# STM32.net
KiCad netlist of a schematic drawn in EasyEDA Pro
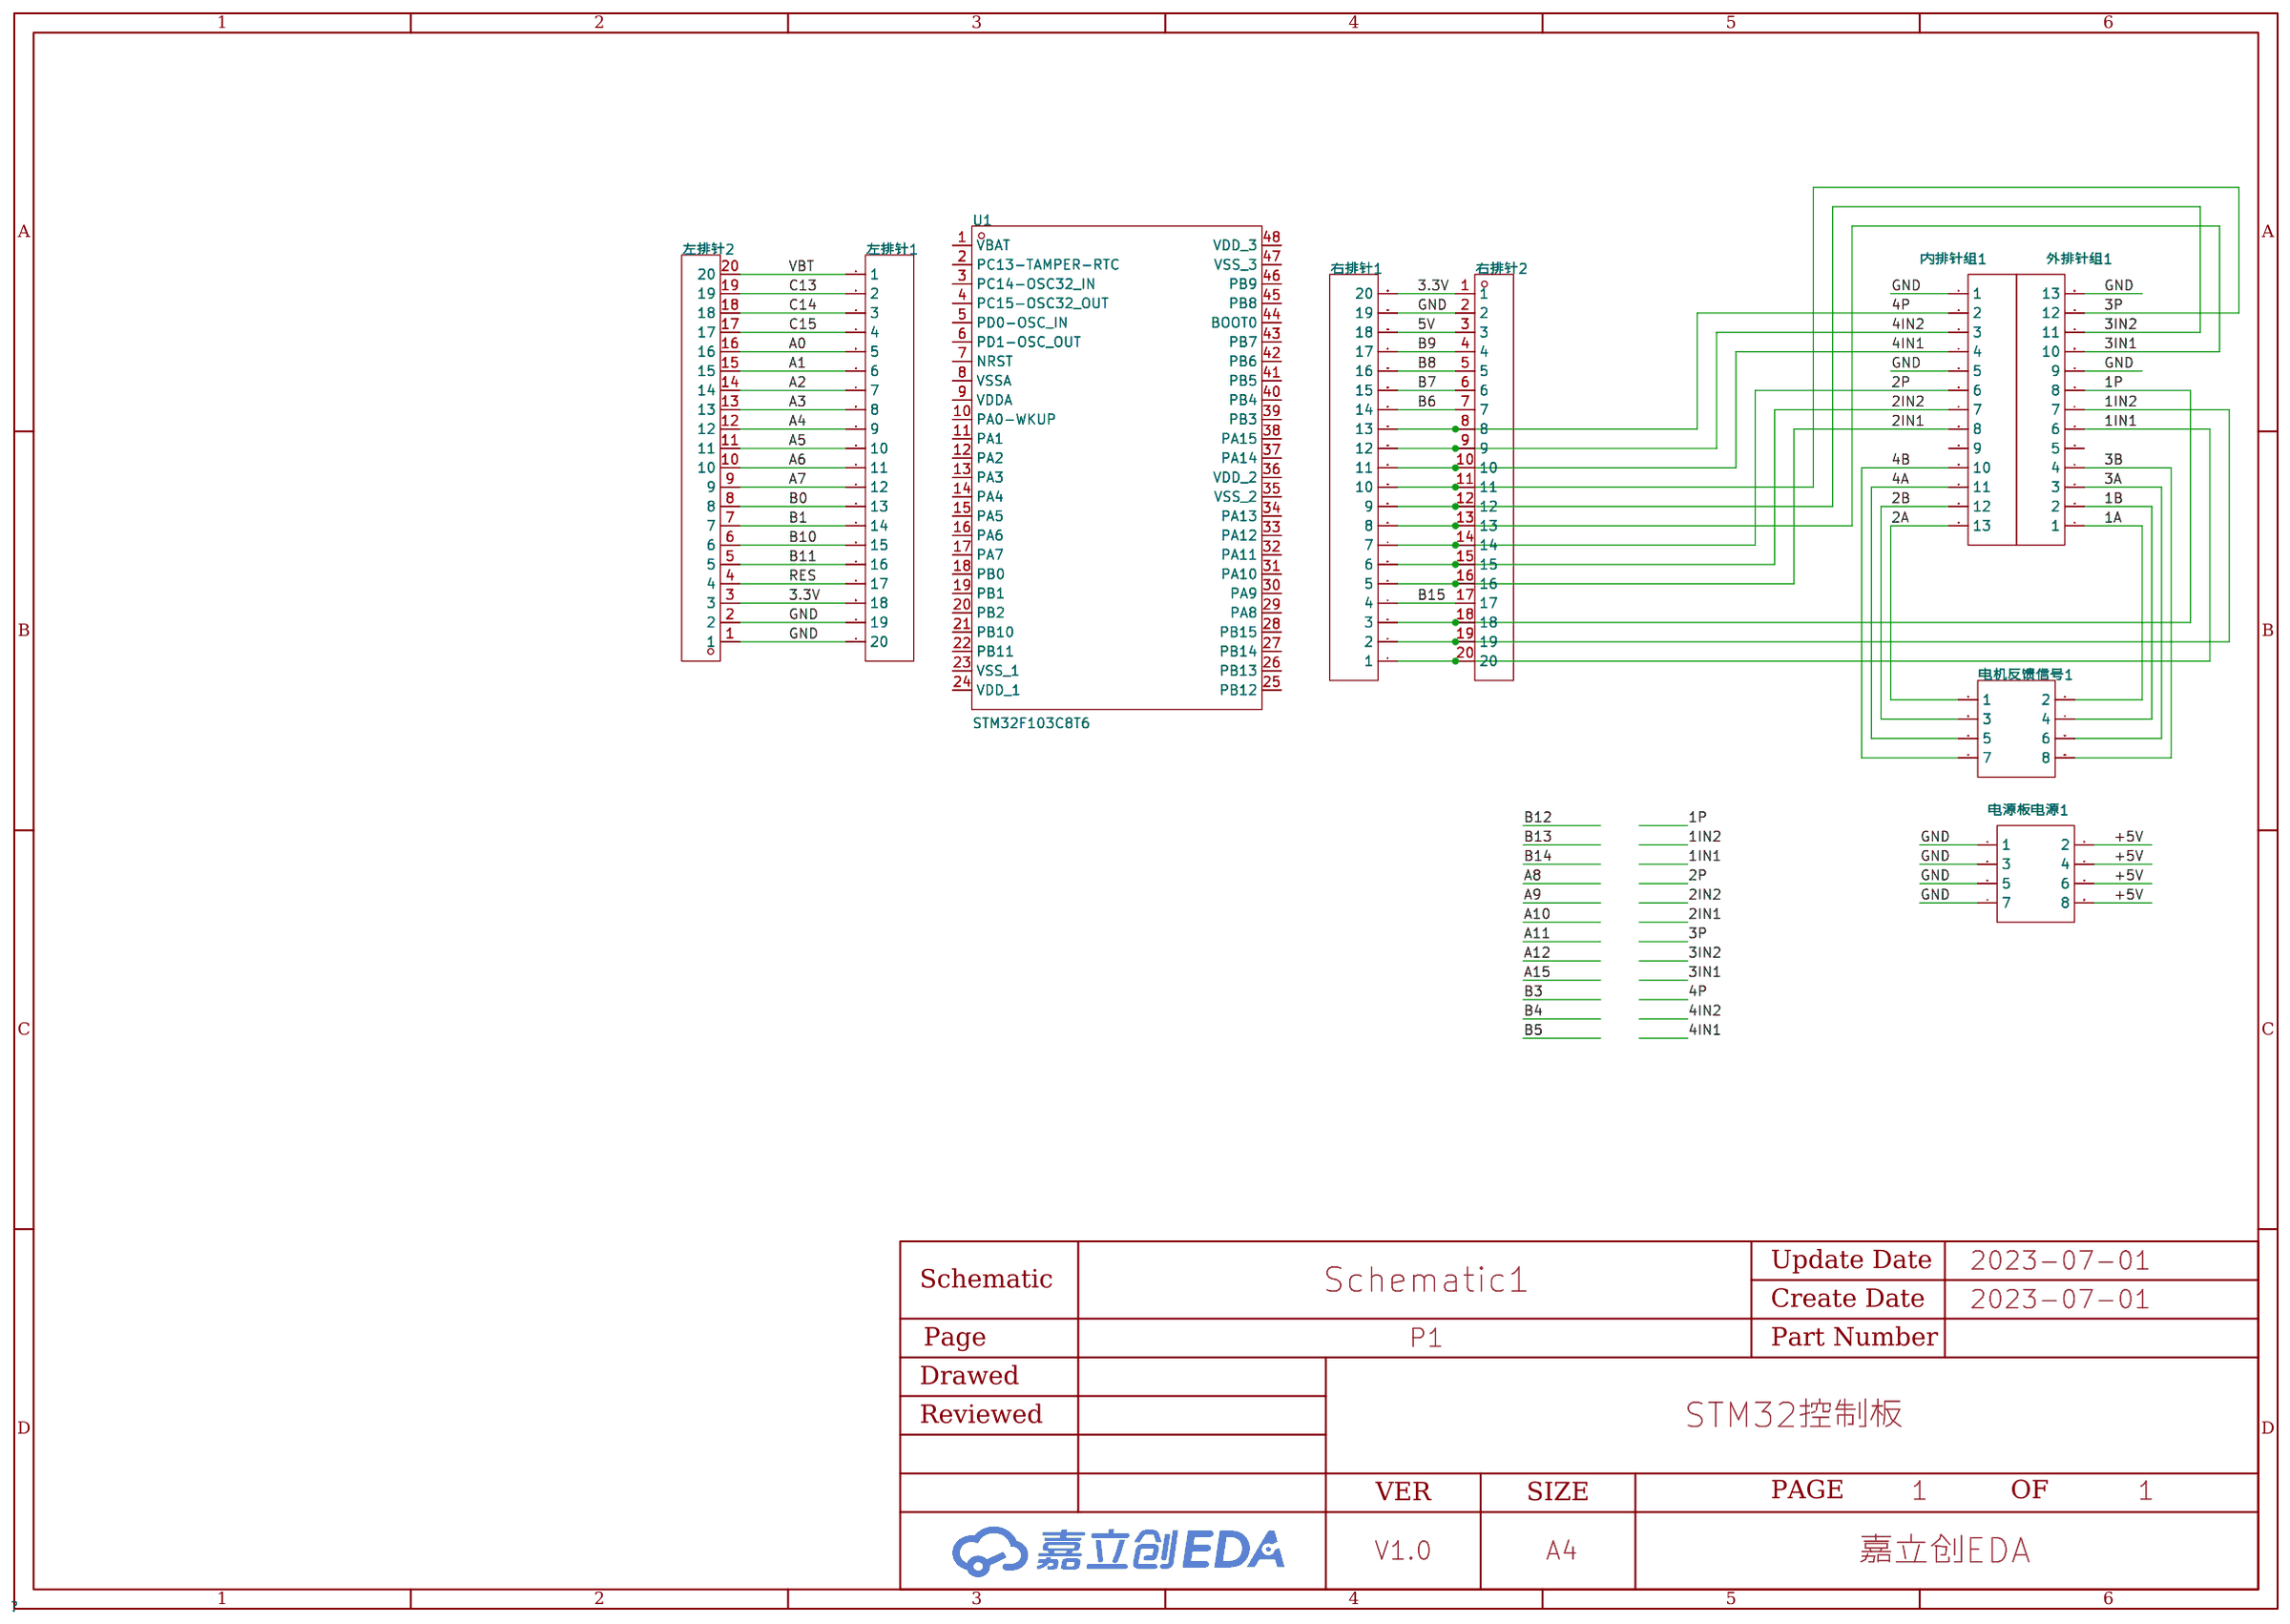
[diagram p0: schematic sheet]

(export (version "E")
  (design (tool "Eeschema 10.0.6"))
  (components
    (comp (ref "U1")
      (value "STM32F103C8T6")
      (footprint "easyedapro:LQFP-48_L7.0-W7.0-P0.50-LS9.0-BL")
      (description "CPU内核:ARM Cortex-M3;CPU最大主频:72MHz;程序存储容量:64KB;程序存储器类型:FLASH;RAM总容量:20KB;GPIO端口数量:37;")
      (fields (field (name "Manufacturer") "ST(意法半导体)"))
      (libsource (lib "easyedapro") (part "STM32F103C8T6"))
    )
    (comp (ref "内排针组1")
      (value "~")
      (footprint "easyedapro:HDR-TH_13P-P2.54-V-F")
      (libsource (lib "easyedapro") (part "HDR-F_2.54_1x13P"))
    )
    (comp (ref "右排针1")
      (value "~")
      (footprint "easyedapro:HDR-TH_20P-P2.54-V-F")
      (libsource (lib "easyedapro") (part "HDR-F_2.54_1x20P"))
    )
    (comp (ref "右排针2")
      (value "~")
      (footprint "easyedapro:HDR-TH_20P-P2.54-V-M-1")
      (libsource (lib "easyedapro") (part "HDR_2.54-1x20P"))
    )
    (comp (ref "外排针组1")
      (value "~")
      (footprint "easyedapro:HDR-TH_13P-P2.54-V-F")
      (libsource (lib "easyedapro") (part "HDR-F_2.54_1x13P"))
    )
    (comp (ref "左排针1")
      (value "~")
      (footprint "easyedapro:HDR-TH_20P-P2.54-V-F")
      (libsource (lib "easyedapro") (part "HDR-F_2.54_1x20P"))
    )
    (comp (ref "左排针2")
      (value "~")
      (footprint "easyedapro:HDR-TH_20P-P2.54-V-M-1")
      (libsource (lib "easyedapro") (part "HDR_2.54-1x20P"))
    )
    (comp (ref "电机反馈信号1")
      (value "~")
      (footprint "easyedapro:HDR-TH_8P-P2.54-V-F-R2-C4-S2.54-1")
      (libsource (lib "easyedapro") (part "HDR-F-2.54_2x4"))
    )
    (comp (ref "电源板电源1")
      (value "~")
      (footprint "easyedapro:HDR-TH_8P-P2.54-V-F-R2-C4-S2.54-1")
      (libsource (lib "easyedapro") (part "HDR-F-2.54_2x4"))
    )
  )
  (nets
    (net (code "1") (name "/+5V") (class "Default")
      (node (ref "电源板电源1") (pin "2") (pinfunction "2_2") (pintype "input"))
      (node (ref "电源板电源1") (pin "4") (pinfunction "4_4") (pintype "input"))
      (node (ref "电源板电源1") (pin "6") (pinfunction "6_6") (pintype "input"))
      (node (ref "电源板电源1") (pin "8") (pinfunction "8_8") (pintype "input"))
    )
    (net (code "2") (name "/1A") (class "Default")
      (node (ref "外排针组1") (pin "1") (pinfunction "1_1") (pintype "input"))
      (node (ref "电机反馈信号1") (pin "2") (pinfunction "2_2") (pintype "input"))
    )
    (net (code "3") (name "/1B") (class "Default")
      (node (ref "外排针组1") (pin "2") (pinfunction "2_2") (pintype "input"))
      (node (ref "电机反馈信号1") (pin "4") (pinfunction "4_4") (pintype "input"))
    )
    (net (code "4") (name "/1IN1") (class "Default")
      (node (ref "右排针1") (pin "1") (pinfunction "1_1") (pintype "input"))
      (node (ref "右排针2") (pin "20") (pinfunction "20_20") (pintype "input"))
      (node (ref "外排针组1") (pin "6") (pinfunction "6_6") (pintype "input"))
    )
    (net (code "5") (name "/1IN2") (class "Default")
      (node (ref "右排针1") (pin "2") (pinfunction "2_2") (pintype "input"))
      (node (ref "右排针2") (pin "19") (pinfunction "19_19") (pintype "input"))
      (node (ref "外排针组1") (pin "7") (pinfunction "7_7") (pintype "input"))
    )
    (net (code "6") (name "/1P") (class "Default")
      (node (ref "右排针1") (pin "3") (pinfunction "3_3") (pintype "input"))
      (node (ref "右排针2") (pin "18") (pinfunction "18_18") (pintype "input"))
      (node (ref "外排针组1") (pin "8") (pinfunction "8_8") (pintype "input"))
    )
    (net (code "7") (name "/2A") (class "Default")
      (node (ref "内排针组1") (pin "13") (pinfunction "13_13") (pintype "input"))
      (node (ref "电机反馈信号1") (pin "1") (pinfunction "1_1") (pintype "input"))
    )
    (net (code "8") (name "/2B") (class "Default")
      (node (ref "内排针组1") (pin "12") (pinfunction "12_12") (pintype "input"))
      (node (ref "电机反馈信号1") (pin "3") (pinfunction "3_3") (pintype "input"))
    )
    (net (code "9") (name "/2IN1") (class "Default")
      (node (ref "内排针组1") (pin "8") (pinfunction "8_8") (pintype "input"))
      (node (ref "右排针1") (pin "5") (pinfunction "5_5") (pintype "input"))
      (node (ref "右排针2") (pin "16") (pinfunction "16_16") (pintype "input"))
    )
    (net (code "10") (name "/2IN2") (class "Default")
      (node (ref "内排针组1") (pin "7") (pinfunction "7_7") (pintype "input"))
      (node (ref "右排针1") (pin "6") (pinfunction "6_6") (pintype "input"))
      (node (ref "右排针2") (pin "15") (pinfunction "15_15") (pintype "input"))
    )
    (net (code "11") (name "/2P") (class "Default")
      (node (ref "内排针组1") (pin "6") (pinfunction "6_6") (pintype "input"))
      (node (ref "右排针1") (pin "7") (pinfunction "7_7") (pintype "input"))
      (node (ref "右排针2") (pin "14") (pinfunction "14_14") (pintype "input"))
    )
    (net (code "12") (name "/3.3V") (class "Default")
      (node (ref "右排针1") (pin "20") (pinfunction "20_20") (pintype "input"))
      (node (ref "右排针2") (pin "1") (pinfunction "1_1") (pintype "input"))
      (node (ref "左排针1") (pin "18") (pinfunction "18_18") (pintype "input"))
      (node (ref "左排针2") (pin "3") (pinfunction "3_3") (pintype "input"))
    )
    (net (code "13") (name "/3A") (class "Default")
      (node (ref "外排针组1") (pin "3") (pinfunction "3_3") (pintype "input"))
      (node (ref "电机反馈信号1") (pin "6") (pinfunction "6_6") (pintype "input"))
    )
    (net (code "14") (name "/3B") (class "Default")
      (node (ref "外排针组1") (pin "4") (pinfunction "4_4") (pintype "input"))
      (node (ref "电机反馈信号1") (pin "8") (pinfunction "8_8") (pintype "input"))
    )
    (net (code "15") (name "/3IN1") (class "Default")
      (node (ref "右排针1") (pin "8") (pinfunction "8_8") (pintype "input"))
      (node (ref "右排针2") (pin "13") (pinfunction "13_13") (pintype "input"))
      (node (ref "外排针组1") (pin "10") (pinfunction "10_10") (pintype "input"))
    )
    (net (code "16") (name "/3IN2") (class "Default")
      (node (ref "右排针1") (pin "9") (pinfunction "9_9") (pintype "input"))
      (node (ref "右排针2") (pin "12") (pinfunction "12_12") (pintype "input"))
      (node (ref "外排针组1") (pin "11") (pinfunction "11_11") (pintype "input"))
    )
    (net (code "17") (name "/3P") (class "Default")
      (node (ref "右排针1") (pin "10") (pinfunction "10_10") (pintype "input"))
      (node (ref "右排针2") (pin "11") (pinfunction "11_11") (pintype "input"))
      (node (ref "外排针组1") (pin "12") (pinfunction "12_12") (pintype "input"))
    )
    (net (code "18") (name "/4A") (class "Default")
      (node (ref "内排针组1") (pin "11") (pinfunction "11_11") (pintype "input"))
      (node (ref "电机反馈信号1") (pin "5") (pinfunction "5_5") (pintype "input"))
    )
    (net (code "19") (name "/4B") (class "Default")
      (node (ref "内排针组1") (pin "10") (pinfunction "10_10") (pintype "input"))
      (node (ref "电机反馈信号1") (pin "7") (pinfunction "7_7") (pintype "input"))
    )
    (net (code "20") (name "/4IN1") (class "Default")
      (node (ref "内排针组1") (pin "4") (pinfunction "4_4") (pintype "input"))
      (node (ref "右排针1") (pin "11") (pinfunction "11_11") (pintype "input"))
      (node (ref "右排针2") (pin "10") (pinfunction "10_10") (pintype "input"))
    )
    (net (code "21") (name "/4IN2") (class "Default")
      (node (ref "内排针组1") (pin "3") (pinfunction "3_3") (pintype "input"))
      (node (ref "右排针1") (pin "12") (pinfunction "12_12") (pintype "input"))
      (node (ref "右排针2") (pin "9") (pinfunction "9_9") (pintype "input"))
    )
    (net (code "22") (name "/4P") (class "Default")
      (node (ref "内排针组1") (pin "2") (pinfunction "2_2") (pintype "input"))
      (node (ref "右排针1") (pin "13") (pinfunction "13_13") (pintype "input"))
      (node (ref "右排针2") (pin "8") (pinfunction "8_8") (pintype "input"))
    )
    (net (code "23") (name "/5V") (class "Default")
      (node (ref "右排针1") (pin "18") (pinfunction "18_18") (pintype "input"))
      (node (ref "右排针2") (pin "3") (pinfunction "3_3") (pintype "input"))
    )
    (net (code "24") (name "/A0") (class "Default")
      (node (ref "左排针1") (pin "5") (pinfunction "5_5") (pintype "input"))
      (node (ref "左排针2") (pin "16") (pinfunction "16_16") (pintype "input"))
    )
    (net (code "25") (name "/A1") (class "Default")
      (node (ref "左排针1") (pin "6") (pinfunction "6_6") (pintype "input"))
      (node (ref "左排针2") (pin "15") (pinfunction "15_15") (pintype "input"))
    )
    (net (code "26") (name "/A2") (class "Default")
      (node (ref "左排针1") (pin "7") (pinfunction "7_7") (pintype "input"))
      (node (ref "左排针2") (pin "14") (pinfunction "14_14") (pintype "input"))
    )
    (net (code "27") (name "/A3") (class "Default")
      (node (ref "左排针1") (pin "8") (pinfunction "8_8") (pintype "input"))
      (node (ref "左排针2") (pin "13") (pinfunction "13_13") (pintype "input"))
    )
    (net (code "28") (name "/A4") (class "Default")
      (node (ref "左排针1") (pin "9") (pinfunction "9_9") (pintype "input"))
      (node (ref "左排针2") (pin "12") (pinfunction "12_12") (pintype "input"))
    )
    (net (code "29") (name "/A5") (class "Default")
      (node (ref "左排针1") (pin "10") (pinfunction "10_10") (pintype "input"))
      (node (ref "左排针2") (pin "11") (pinfunction "11_11") (pintype "input"))
    )
    (net (code "30") (name "/A6") (class "Default")
      (node (ref "左排针1") (pin "11") (pinfunction "11_11") (pintype "input"))
      (node (ref "左排针2") (pin "10") (pinfunction "10_10") (pintype "input"))
    )
    (net (code "31") (name "/A7") (class "Default")
      (node (ref "左排针1") (pin "12") (pinfunction "12_12") (pintype "input"))
      (node (ref "左排针2") (pin "9") (pinfunction "9_9") (pintype "input"))
    )
    (net (code "38") (name "/B0") (class "Default")
      (node (ref "左排针1") (pin "13") (pinfunction "13_13") (pintype "input"))
      (node (ref "左排针2") (pin "8") (pinfunction "8_8") (pintype "input"))
    )
    (net (code "39") (name "/B1") (class "Default")
      (node (ref "左排针1") (pin "14") (pinfunction "14_14") (pintype "input"))
      (node (ref "左排针2") (pin "7") (pinfunction "7_7") (pintype "input"))
    )
    (net (code "43") (name "/B6") (class "Default")
      (node (ref "右排针1") (pin "14") (pinfunction "14_14") (pintype "input"))
      (node (ref "右排针2") (pin "7") (pinfunction "7_7") (pintype "input"))
    )
    (net (code "44") (name "/B7") (class "Default")
      (node (ref "右排针1") (pin "15") (pinfunction "15_15") (pintype "input"))
      (node (ref "右排针2") (pin "6") (pinfunction "6_6") (pintype "input"))
    )
    (net (code "45") (name "/B8") (class "Default")
      (node (ref "右排针1") (pin "16") (pinfunction "16_16") (pintype "input"))
      (node (ref "右排针2") (pin "5") (pinfunction "5_5") (pintype "input"))
    )
    (net (code "46") (name "/B9") (class "Default")
      (node (ref "右排针1") (pin "17") (pinfunction "17_17") (pintype "input"))
      (node (ref "右排针2") (pin "4") (pinfunction "4_4") (pintype "input"))
    )
    (net (code "47") (name "/B10") (class "Default")
      (node (ref "左排针1") (pin "15") (pinfunction "15_15") (pintype "input"))
      (node (ref "左排针2") (pin "6") (pinfunction "6_6") (pintype "input"))
    )
    (net (code "48") (name "/B11") (class "Default")
      (node (ref "左排针1") (pin "16") (pinfunction "16_16") (pintype "input"))
      (node (ref "左排针2") (pin "5") (pinfunction "5_5") (pintype "input"))
    )
    (net (code "52") (name "/B15") (class "Default")
      (node (ref "右排针1") (pin "4") (pinfunction "4_4") (pintype "input"))
      (node (ref "右排针2") (pin "17") (pinfunction "17_17") (pintype "input"))
    )
    (net (code "53") (name "/C13") (class "Default")
      (node (ref "左排针1") (pin "2") (pinfunction "2_2") (pintype "input"))
      (node (ref "左排针2") (pin "19") (pinfunction "19_19") (pintype "input"))
    )
    (net (code "54") (name "/C14") (class "Default")
      (node (ref "左排针1") (pin "3") (pinfunction "3_3") (pintype "input"))
      (node (ref "左排针2") (pin "18") (pinfunction "18_18") (pintype "input"))
    )
    (net (code "55") (name "/C15") (class "Default")
      (node (ref "左排针1") (pin "4") (pinfunction "4_4") (pintype "input"))
      (node (ref "左排针2") (pin "17") (pinfunction "17_17") (pintype "input"))
    )
    (net (code "56") (name "/GND") (class "Default")
      (node (ref "内排针组1") (pin "1") (pinfunction "1_1") (pintype "input"))
      (node (ref "内排针组1") (pin "5") (pinfunction "5_5") (pintype "input"))
      (node (ref "右排针1") (pin "19") (pinfunction "19_19") (pintype "input"))
      (node (ref "右排针2") (pin "2") (pinfunction "2_2") (pintype "input"))
      (node (ref "外排针组1") (pin "13") (pinfunction "13_13") (pintype "input"))
      (node (ref "外排针组1") (pin "9") (pinfunction "9_9") (pintype "input"))
      (node (ref "左排针1") (pin "19") (pinfunction "19_19") (pintype "input"))
      (node (ref "左排针1") (pin "20") (pinfunction "20_20") (pintype "input"))
      (node (ref "左排针2") (pin "1") (pinfunction "1_1") (pintype "input"))
      (node (ref "左排针2") (pin "2") (pinfunction "2_2") (pintype "input"))
      (node (ref "电源板电源1") (pin "1") (pinfunction "1_1") (pintype "input"))
      (node (ref "电源板电源1") (pin "3") (pinfunction "3_3") (pintype "input"))
      (node (ref "电源板电源1") (pin "5") (pinfunction "5_5") (pintype "input"))
      (node (ref "电源板电源1") (pin "7") (pinfunction "7_7") (pintype "input"))
    )
    (net (code "57") (name "/RES") (class "Default")
      (node (ref "左排针1") (pin "17") (pinfunction "17_17") (pintype "input"))
      (node (ref "左排针2") (pin "4") (pinfunction "4_4") (pintype "input"))
    )
    (net (code "58") (name "/VBT") (class "Default")
      (node (ref "左排针1") (pin "1") (pinfunction "1_1") (pintype "input"))
      (node (ref "左排针2") (pin "20") (pinfunction "20_20") (pintype "input"))
    )
    (net (code "59") (name "unconnected-(U1-BOOT0-Pad44)") (class "Default")
      (node (ref "U1") (pin "44") (pinfunction "BOOT0_44") (pintype "input"))
    )
    (net (code "60") (name "unconnected-(U1-NRST-Pad7)") (class "Default")
      (node (ref "U1") (pin "7") (pinfunction "NRST_7") (pintype "input"))
    )
    (net (code "61") (name "unconnected-(U1-PA0-WKUP-Pad10)") (class "Default")
      (node (ref "U1") (pin "10") (pinfunction "PA0-WKUP_10") (pintype "input"))
    )
    (net (code "62") (name "unconnected-(U1-PA1-Pad11)") (class "Default")
      (node (ref "U1") (pin "11") (pinfunction "PA1_11") (pintype "input"))
    )
    (net (code "63") (name "unconnected-(U1-PA2-Pad12)") (class "Default")
      (node (ref "U1") (pin "12") (pinfunction "PA2_12") (pintype "input"))
    )
    (net (code "64") (name "unconnected-(U1-PA3-Pad13)") (class "Default")
      (node (ref "U1") (pin "13") (pinfunction "PA3_13") (pintype "input"))
    )
    (net (code "65") (name "unconnected-(U1-PA4-Pad14)") (class "Default")
      (node (ref "U1") (pin "14") (pinfunction "PA4_14") (pintype "input"))
    )
    (net (code "66") (name "unconnected-(U1-PA5-Pad15)") (class "Default")
      (node (ref "U1") (pin "15") (pinfunction "PA5_15") (pintype "input"))
    )
    (net (code "67") (name "unconnected-(U1-PA6-Pad16)") (class "Default")
      (node (ref "U1") (pin "16") (pinfunction "PA6_16") (pintype "input"))
    )
    (net (code "68") (name "unconnected-(U1-PA7-Pad17)") (class "Default")
      (node (ref "U1") (pin "17") (pinfunction "PA7_17") (pintype "input"))
    )
    (net (code "69") (name "unconnected-(U1-PA8-Pad29)") (class "Default")
      (node (ref "U1") (pin "29") (pinfunction "PA8_29") (pintype "input"))
    )
    (net (code "70") (name "unconnected-(U1-PA9-Pad30)") (class "Default")
      (node (ref "U1") (pin "30") (pinfunction "PA9_30") (pintype "input"))
    )
    (net (code "71") (name "unconnected-(U1-PA10-Pad31)") (class "Default")
      (node (ref "U1") (pin "31") (pinfunction "PA10_31") (pintype "input"))
    )
    (net (code "72") (name "unconnected-(U1-PA11-Pad32)") (class "Default")
      (node (ref "U1") (pin "32") (pinfunction "PA11_32") (pintype "input"))
    )
    (net (code "73") (name "unconnected-(U1-PA12-Pad33)") (class "Default")
      (node (ref "U1") (pin "33") (pinfunction "PA12_33") (pintype "input"))
    )
    (net (code "74") (name "unconnected-(U1-PA13-Pad34)") (class "Default")
      (node (ref "U1") (pin "34") (pinfunction "PA13_34") (pintype "input"))
    )
    (net (code "75") (name "unconnected-(U1-PA14-Pad37)") (class "Default")
      (node (ref "U1") (pin "37") (pinfunction "PA14_37") (pintype "input"))
    )
    (net (code "76") (name "unconnected-(U1-PA15-Pad38)") (class "Default")
      (node (ref "U1") (pin "38") (pinfunction "PA15_38") (pintype "input"))
    )
    (net (code "77") (name "unconnected-(U1-PB0-Pad18)") (class "Default")
      (node (ref "U1") (pin "18") (pinfunction "PB0_18") (pintype "input"))
    )
    (net (code "78") (name "unconnected-(U1-PB1-Pad19)") (class "Default")
      (node (ref "U1") (pin "19") (pinfunction "PB1_19") (pintype "input"))
    )
    (net (code "79") (name "unconnected-(U1-PB2-Pad20)") (class "Default")
      (node (ref "U1") (pin "20") (pinfunction "PB2_20") (pintype "input"))
    )
    (net (code "80") (name "unconnected-(U1-PB3-Pad39)") (class "Default")
      (node (ref "U1") (pin "39") (pinfunction "PB3_39") (pintype "input"))
    )
    (net (code "81") (name "unconnected-(U1-PB4-Pad40)") (class "Default")
      (node (ref "U1") (pin "40") (pinfunction "PB4_40") (pintype "input"))
    )
    (net (code "82") (name "unconnected-(U1-PB5-Pad41)") (class "Default")
      (node (ref "U1") (pin "41") (pinfunction "PB5_41") (pintype "input"))
    )
    (net (code "83") (name "unconnected-(U1-PB6-Pad42)") (class "Default")
      (node (ref "U1") (pin "42") (pinfunction "PB6_42") (pintype "input"))
    )
    (net (code "84") (name "unconnected-(U1-PB7-Pad43)") (class "Default")
      (node (ref "U1") (pin "43") (pinfunction "PB7_43") (pintype "input"))
    )
    (net (code "85") (name "unconnected-(U1-PB8-Pad45)") (class "Default")
      (node (ref "U1") (pin "45") (pinfunction "PB8_45") (pintype "input"))
    )
    (net (code "86") (name "unconnected-(U1-PB9-Pad46)") (class "Default")
      (node (ref "U1") (pin "46") (pinfunction "PB9_46") (pintype "input"))
    )
    (net (code "87") (name "unconnected-(U1-PB10-Pad21)") (class "Default")
      (node (ref "U1") (pin "21") (pinfunction "PB10_21") (pintype "input"))
    )
    (net (code "88") (name "unconnected-(U1-PB11-Pad22)") (class "Default")
      (node (ref "U1") (pin "22") (pinfunction "PB11_22") (pintype "input"))
    )
    (net (code "89") (name "unconnected-(U1-PB12-Pad25)") (class "Default")
      (node (ref "U1") (pin "25") (pinfunction "PB12_25") (pintype "input"))
    )
    (net (code "90") (name "unconnected-(U1-PB13-Pad26)") (class "Default")
      (node (ref "U1") (pin "26") (pinfunction "PB13_26") (pintype "input"))
    )
    (net (code "91") (name "unconnected-(U1-PB14-Pad27)") (class "Default")
      (node (ref "U1") (pin "27") (pinfunction "PB14_27") (pintype "input"))
    )
    (net (code "92") (name "unconnected-(U1-PB15-Pad28)") (class "Default")
      (node (ref "U1") (pin "28") (pinfunction "PB15_28") (pintype "input"))
    )
    (net (code "93") (name "unconnected-(U1-PC13-TAMPER-RTC-Pad2)") (class "Default")
      (node (ref "U1") (pin "2") (pinfunction "PC13-TAMPER-RTC_2") (pintype "input"))
    )
    (net (code "94") (name "unconnected-(U1-PC14-OSC32_IN-Pad3)") (class "Default")
      (node (ref "U1") (pin "3") (pinfunction "PC14-OSC32_IN_3") (pintype "input"))
    )
    (net (code "95") (name "unconnected-(U1-PC15-OSC32_OUT-Pad4)") (class "Default")
      (node (ref "U1") (pin "4") (pinfunction "PC15-OSC32_OUT_4") (pintype "input"))
    )
    (net (code "96") (name "unconnected-(U1-PD0-OSC_IN-Pad5)") (class "Default")
      (node (ref "U1") (pin "5") (pinfunction "PD0-OSC_IN_5") (pintype "input"))
    )
    (net (code "97") (name "unconnected-(U1-PD1-OSC_OUT-Pad6)") (class "Default")
      (node (ref "U1") (pin "6") (pinfunction "PD1-OSC_OUT_6") (pintype "input"))
    )
    (net (code "98") (name "unconnected-(U1-VBAT-Pad1)") (class "Default")
      (node (ref "U1") (pin "1") (pinfunction "VBAT_1") (pintype "input"))
    )
    (net (code "99") (name "unconnected-(U1-VDDA-Pad9)") (class "Default")
      (node (ref "U1") (pin "9") (pinfunction "VDDA_9") (pintype "input"))
    )
    (net (code "100") (name "unconnected-(U1-VDD_1-Pad24)") (class "Default")
      (node (ref "U1") (pin "24") (pinfunction "VDD_1_24") (pintype "input"))
    )
    (net (code "101") (name "unconnected-(U1-VDD_2-Pad36)") (class "Default")
      (node (ref "U1") (pin "36") (pinfunction "VDD_2_36") (pintype "input"))
    )
    (net (code "102") (name "unconnected-(U1-VDD_3-Pad48)") (class "Default")
      (node (ref "U1") (pin "48") (pinfunction "VDD_3_48") (pintype "input"))
    )
    (net (code "103") (name "unconnected-(U1-VSSA-Pad8)") (class "Default")
      (node (ref "U1") (pin "8") (pinfunction "VSSA_8") (pintype "input"))
    )
    (net (code "104") (name "unconnected-(U1-VSS_1-Pad23)") (class "Default")
      (node (ref "U1") (pin "23") (pinfunction "VSS_1_23") (pintype "input"))
    )
    (net (code "105") (name "unconnected-(U1-VSS_2-Pad35)") (class "Default")
      (node (ref "U1") (pin "35") (pinfunction "VSS_2_35") (pintype "input"))
    )
    (net (code "106") (name "unconnected-(U1-VSS_3-Pad47)") (class "Default")
      (node (ref "U1") (pin "47") (pinfunction "VSS_3_47") (pintype "input"))
    )
    (net (code "107") (name "unconnected-(内排针组1-Pad9)") (class "Default")
      (node (ref "内排针组1") (pin "9") (pinfunction "9_9") (pintype "input"))
    )
    (net (code "108") (name "unconnected-(外排针组1-Pad5)") (class "Default")
      (node (ref "外排针组1") (pin "5") (pinfunction "5_5") (pintype "input"))
    )
  )
)
